# design.net
KiCad netlist of a schematic drawn in Altium Designer
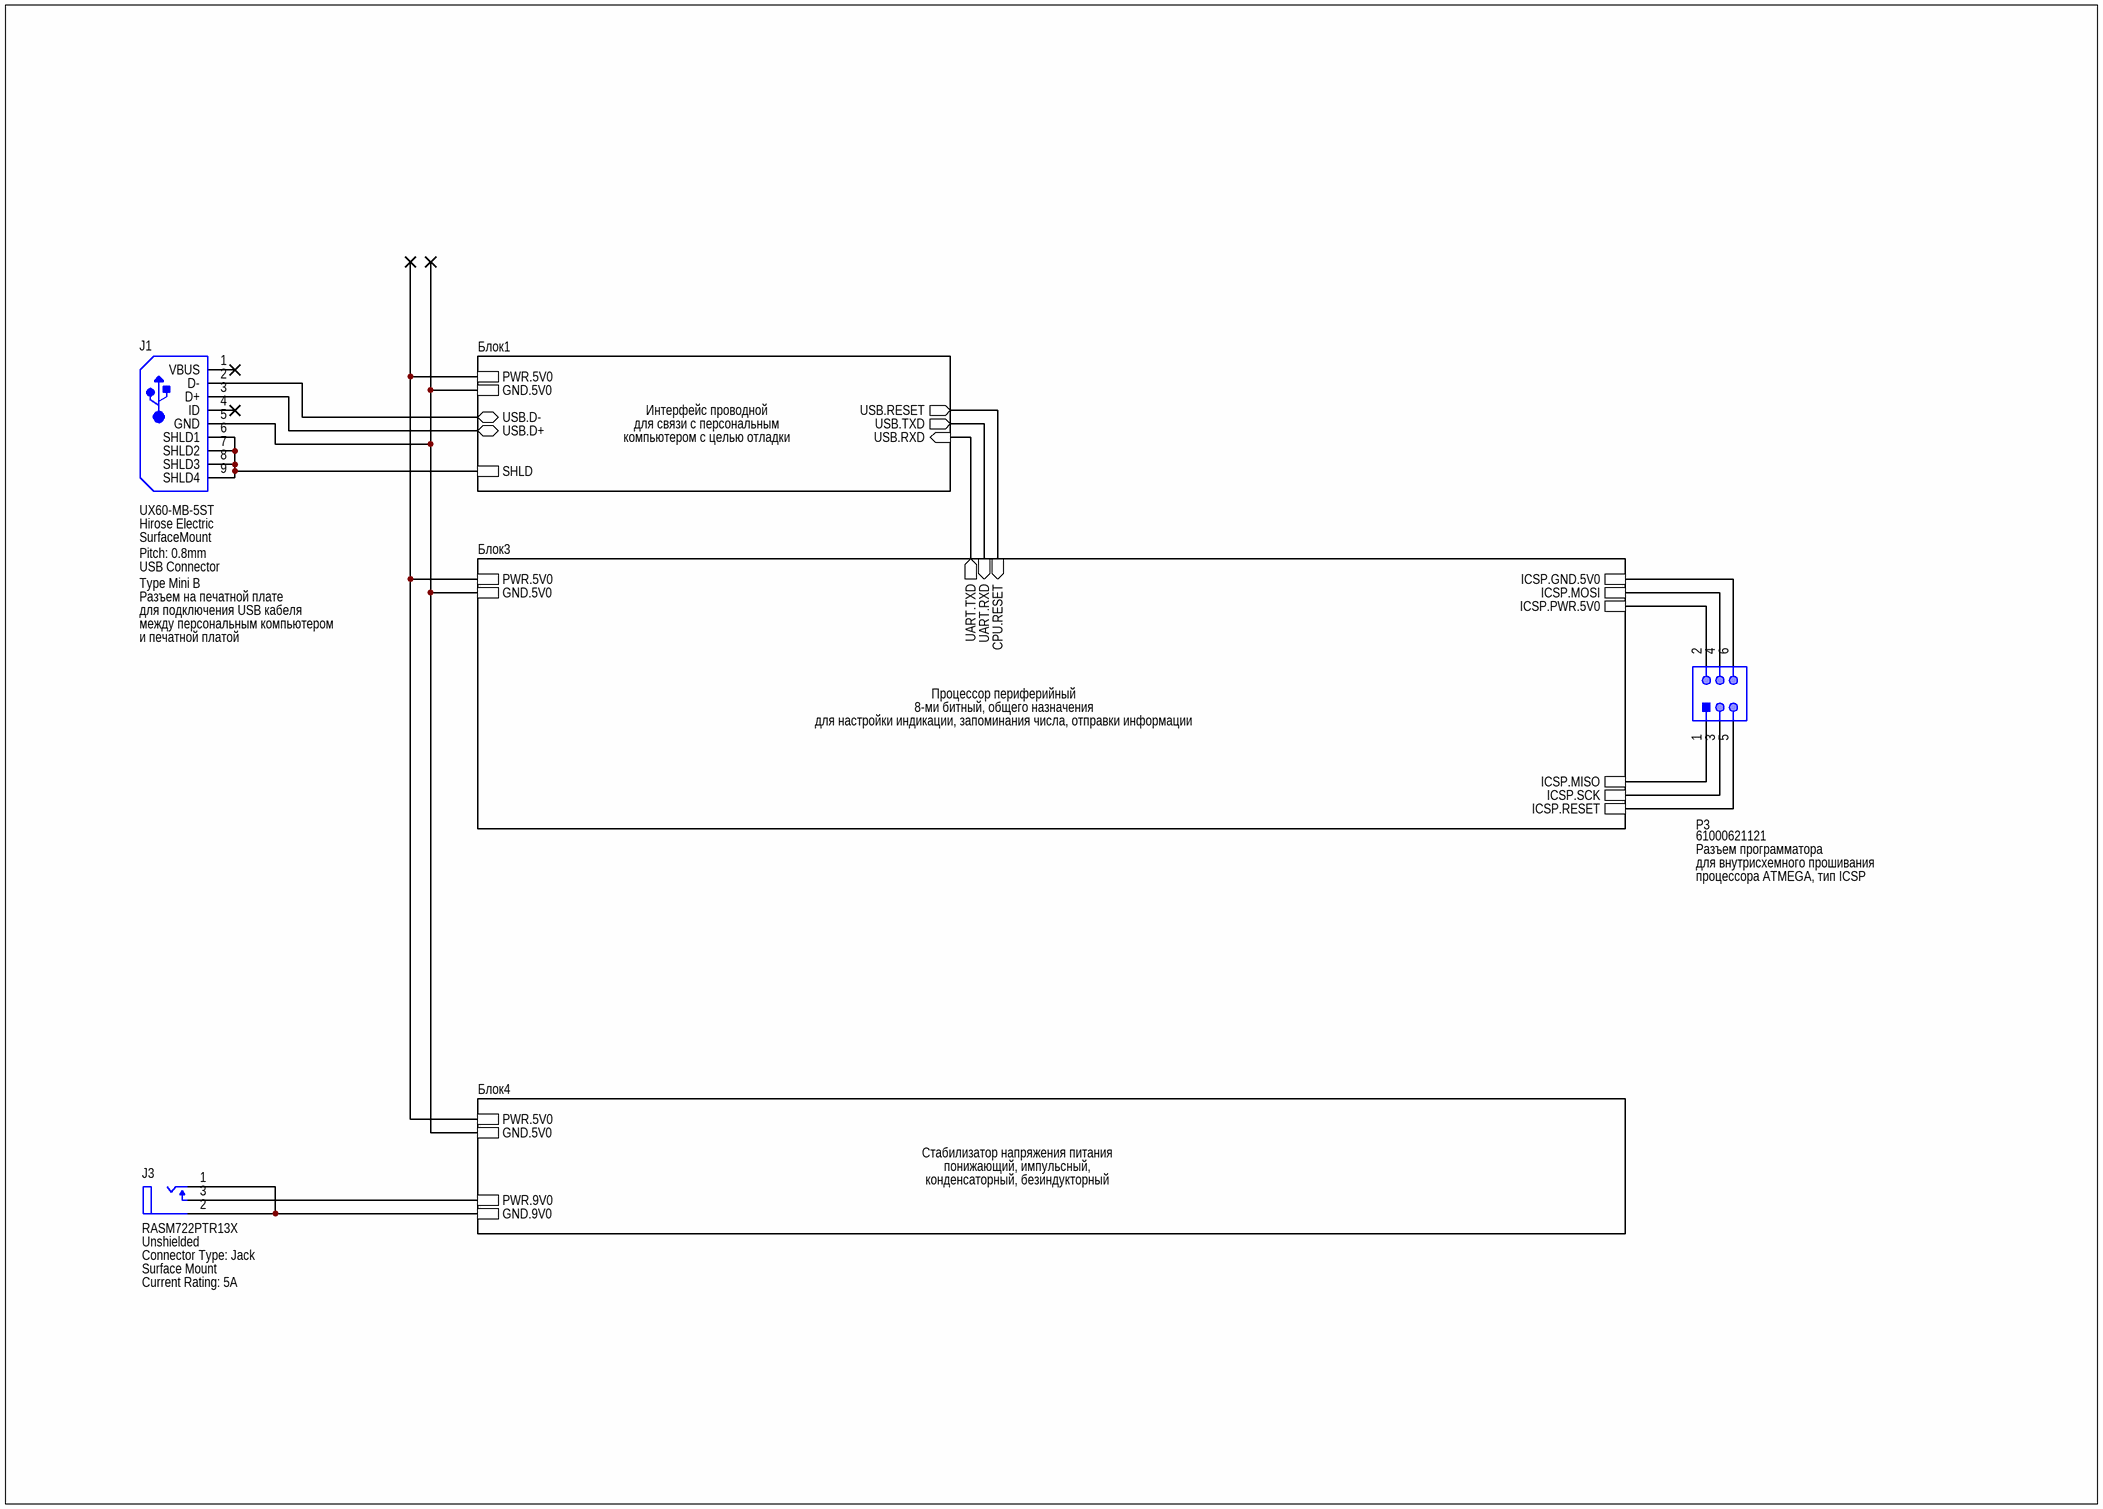
[diagram p0: Архитектура.SchDoc]

(export (version "E")
  (design (tool "Eeschema 10.0.6"))
  (components
    (comp (ref "J1")
      (value "UX60-MB-5ST")
      (footprint "HIRO-UX60-MB-5ST_V")
      (description "USB Connector Mini B Type, 1 A, 5 V AC, -30 to 75 degC, 5-Pin SMD, RoHS, Tape and Reel")
      (fields
        (field (name "MANUFACTURER") "Hirose Electric")
        (field (name "TERMINATION") "SurfaceMount")
        (field (name "PITCH") "0.8mm")
        (field (name "PARAMETER 1") "USB Connector")
        (field (name "PARAMETER 2") "Type Mini B")
        (field (name "PARAMETER 3") "Разъем на печатной плате")
        (field (name "PARAMETER 4") "для подключения USB кабеля")
        (field (name "PARAMETER 5") "между персональным компьютером")
        (field (name "PARAMETER 6") "и печатной платой")
      )
      (libsource (lib "Altium Content Vault") (part "USB-5-4SHLD"))
    )
    (comp (ref "J3")
      (value "RASM722PTR13X")
      (footprint "FP-RASM722PTR13X-MFG")
      (description "CONN PWR JACK 2.1X5.5MM SOLDER")
      (fields
        (field (name "SHIELDING") "Unshielded")
        (field (name "CONNECTOR TYPE") "Jack")
        (field (name "MOUNT") "Surface Mount")
        (field (name "CURRENT RATING") "5A")
      )
      (libsource (lib "Altium Content Vault") (part "69023cd999ddc70d2a190894d9bbb58"))
    )
    (comp (ref "P3")
      (value "61000621121")
      (footprint "61000621121")
      (description "SMT Vertical Pin Header WR-PHD, Pitch 2.54 mm, Dual Row, 6 pins")
      (fields
        (field (name "MANUFACTURER") "Wurth Elektronik")
        (field (name "PARAMETER 1") "Разъем программатора")
        (field (name "PARAMETER 2") "для внутрисхемного прошивания")
        (field (name "PARAMETER 3") "процессора ATMEGA, тип ICSP")
        (field (name "PUBLISHER") "WurthElektronik")
      )
      (libsource (lib "Altium Content Vault") (part "WE-CN-2P-M-R6"))
    )
  )
  (nets
    (net (code "1") (name "/GND.5V0") (class "Default")
      (node (ref "J1") (pin "5") (pinfunction "GND_5") (pintype "power_in+no_connect"))
    )
    (net (code "2") (name "/GND.9V0") (class "Default")
      (node (ref "J3") (pin "1") (pinfunction "TIP_TERMINAL(CENTER_PIN)_1") (pintype "passive"))
      (node (ref "J3") (pin "2") (pinfunction "SLEEVE_TERMINAL_2") (pintype "passive"))
    )
    (net (code "3") (name "/ICSP.GND.5V0") (class "Default")
      (node (ref "P3") (pin "6") (pinfunction "6_6") (pintype "passive"))
    )
    (net (code "4") (name "/ICSP.MISO") (class "Default")
      (node (ref "P3") (pin "1") (pinfunction "1_1") (pintype "passive"))
    )
    (net (code "5") (name "/ICSP.MOSI") (class "Default")
      (node (ref "P3") (pin "4") (pinfunction "4_4") (pintype "passive"))
    )
    (net (code "6") (name "/ICSP.PWR.5V0") (class "Default")
      (node (ref "P3") (pin "2") (pinfunction "2_2") (pintype "passive"))
    )
    (net (code "7") (name "/ICSP.RESET") (class "Default")
      (node (ref "P3") (pin "5") (pinfunction "5_5") (pintype "passive"))
    )
    (net (code "8") (name "/ICSP.SCK") (class "Default")
      (node (ref "P3") (pin "3") (pinfunction "3_3") (pintype "passive"))
    )
    (net (code "10") (name "/PWR.9V0") (class "Default")
      (node (ref "J3") (pin "3") (pinfunction "SHUNT_TERMINAL_3") (pintype "passive"))
    )
    (net (code "11") (name "/SHLD") (class "Default")
      (node (ref "J1") (pin "6") (pinfunction "SHLD1_6") (pintype "passive"))
      (node (ref "J1") (pin "7") (pinfunction "SHLD2_7") (pintype "passive"))
      (node (ref "J1") (pin "8") (pinfunction "SHLD3_8") (pintype "passive"))
      (node (ref "J1") (pin "9") (pinfunction "SHLD4_9") (pintype "passive"))
    )
    (net (code "13") (name "/USB.D+") (class "Default")
      (node (ref "J1") (pin "3") (pinfunction "D+_3") (pintype "passive"))
    )
    (net (code "14") (name "/USB.D-") (class "Default")
      (node (ref "J1") (pin "2") (pinfunction "D-_2") (pintype "passive"))
    )
    (net (code "17") (name "unconnected-(J1-ID-Pad4)") (class "Default")
      (node (ref "J1") (pin "4") (pinfunction "ID_4") (pintype "passive+no_connect"))
    )
    (net (code "18") (name "unconnected-(J1-VBUS-Pad1)") (class "Default")
      (node (ref "J1") (pin "1") (pinfunction "VBUS_1") (pintype "power_in+no_connect"))
    )
  )
)
